# 20210903BuckModel.net
KiCad netlist of a schematic drawn in EasyEDA Pro
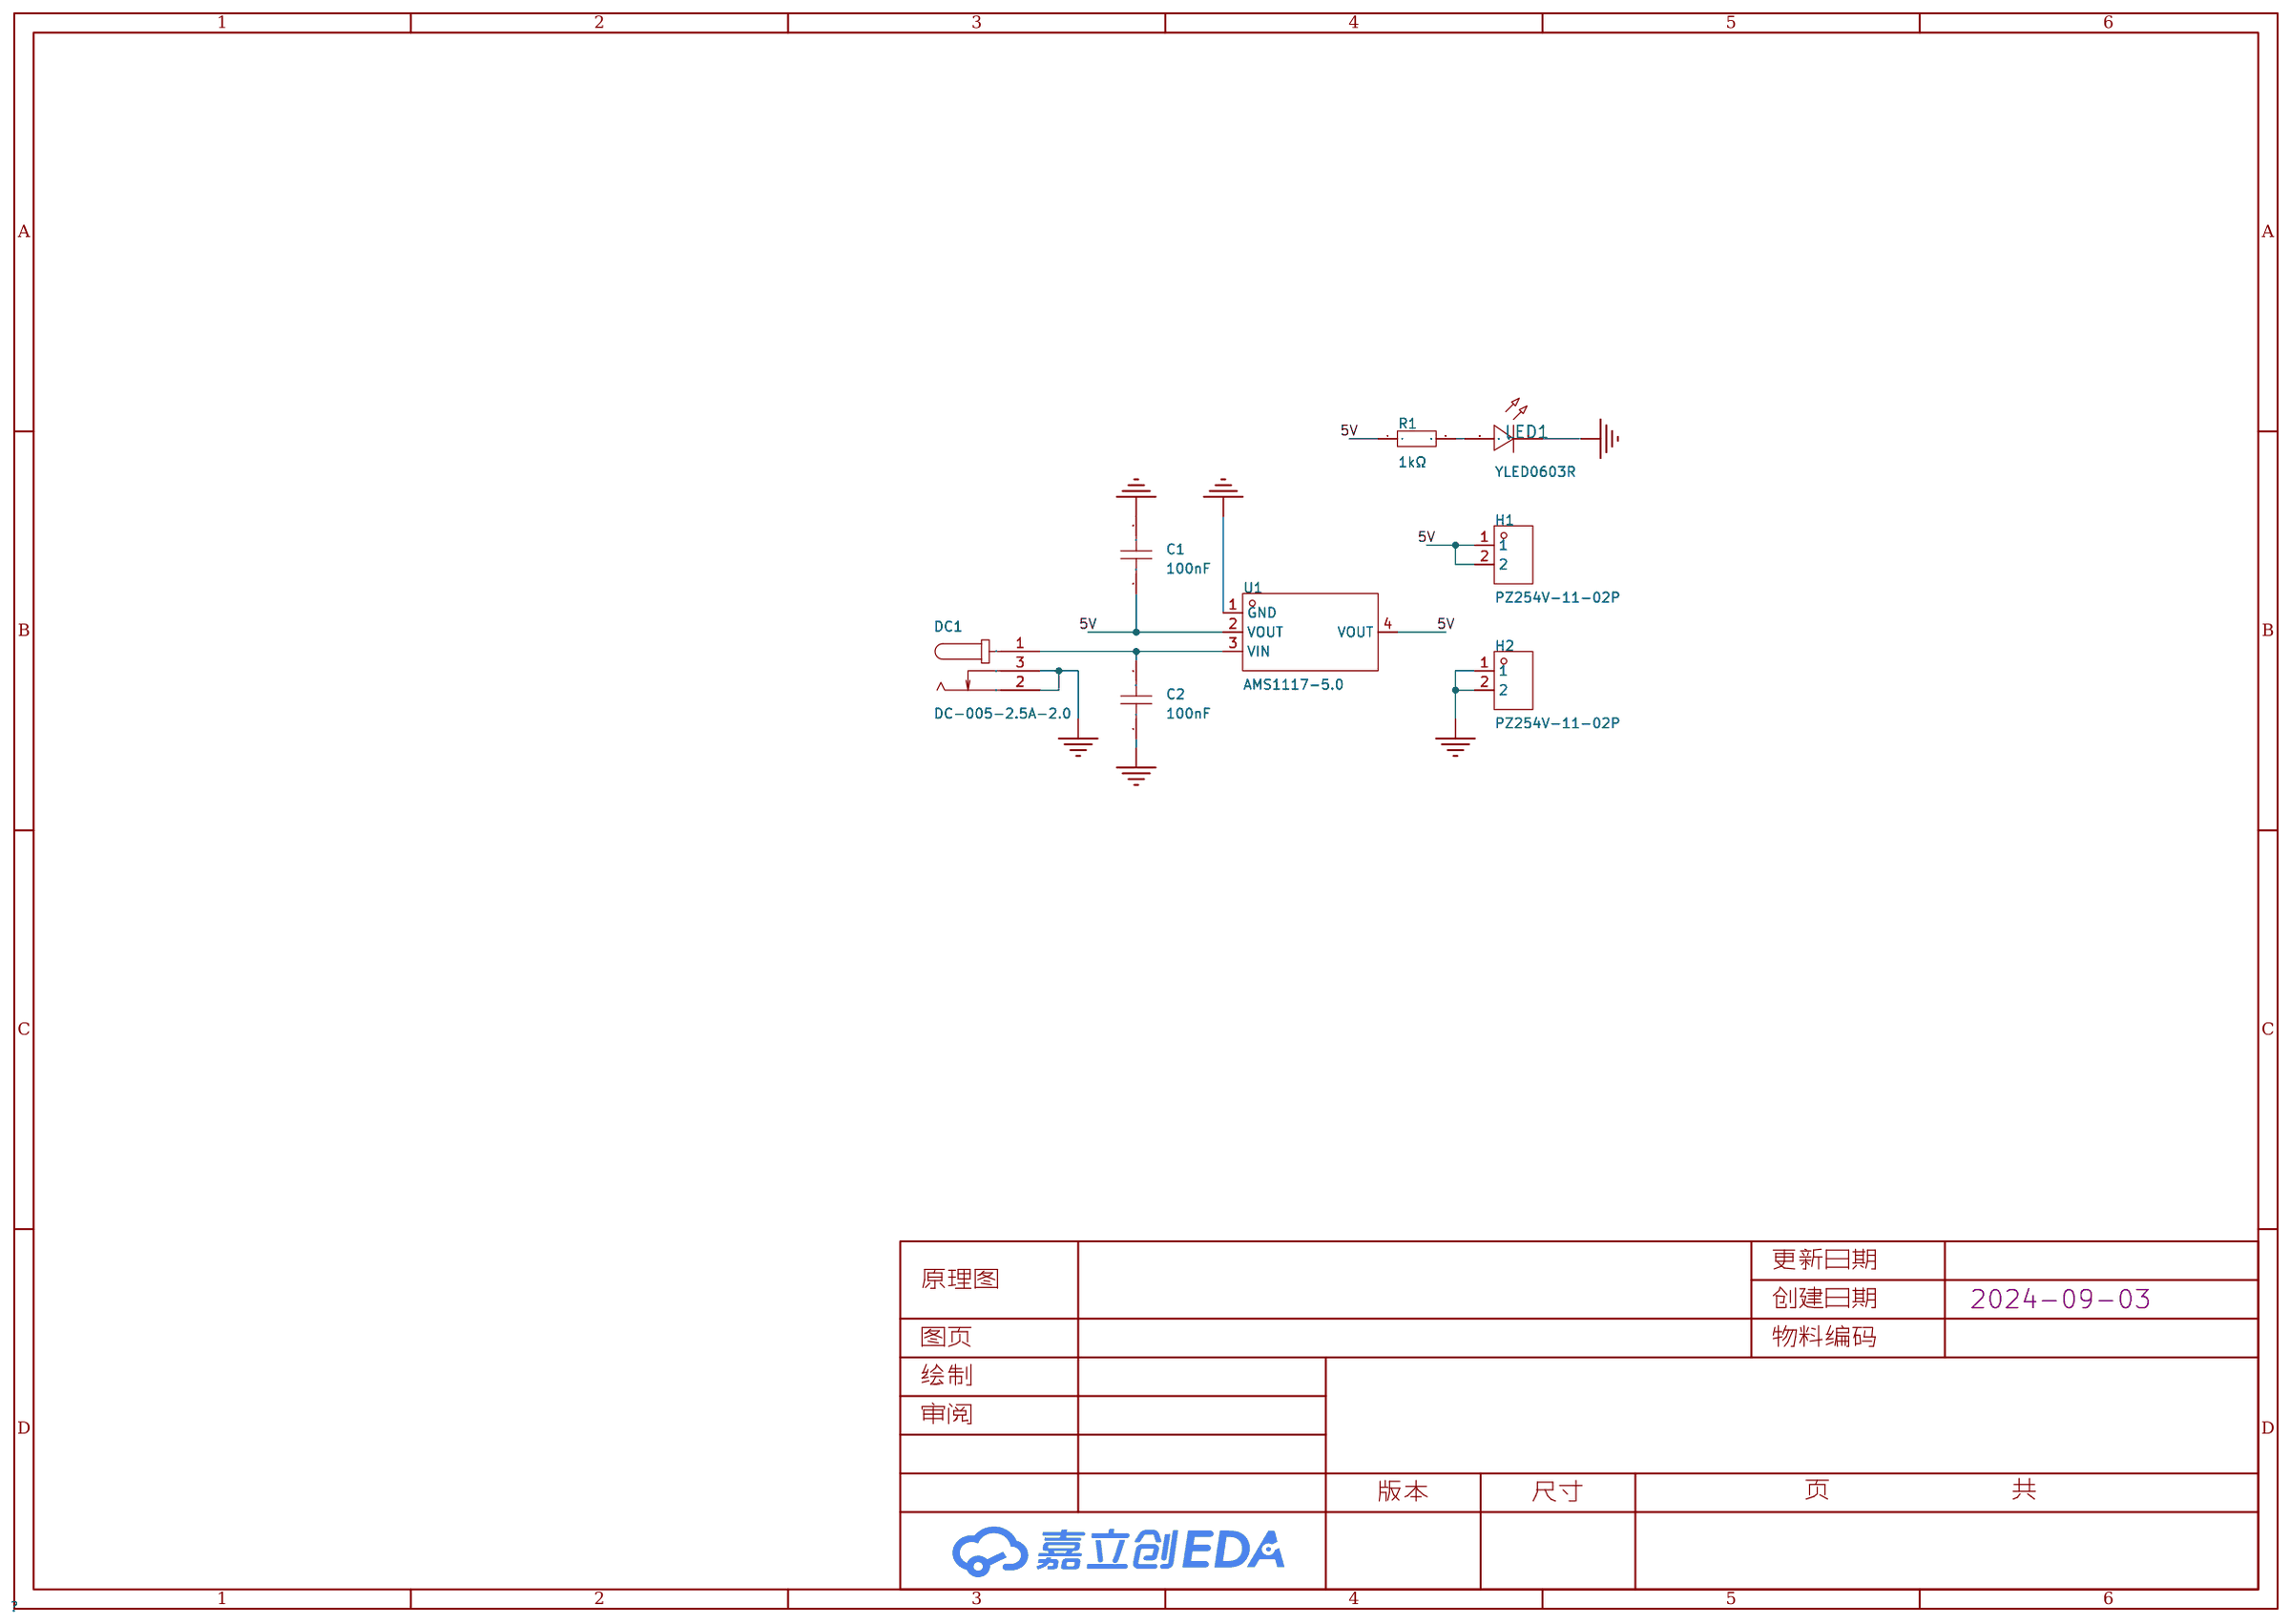
[diagram p0: schematic sheet]

(export (version "E")
  (design (tool "Eeschema 10.0.6"))
  (components
    (comp (ref "C1")
      (value "100nF")
      (footprint "easyedapro:C0402")
      (description "容值:100nF;精度:±10%;额定电压:16V;材质(温度系数):X7R;")
      (fields
        (field (name "Manufacturer Part") "CC0402KRX7R7BB104")
        (field (name "Manufacturer") "YAGEO(国巨)")
      )
      (libsource (lib "easyedapro") (part "CC0402KRX7R7BB104"))
    )
    (comp (ref "C2")
      (value "100nF")
      (footprint "easyedapro:C0402")
      (description "容值:100nF;精度:±10%;额定电压:16V;材质(温度系数):X7R;")
      (fields
        (field (name "Manufacturer Part") "CC0402KRX7R7BB104")
        (field (name "Manufacturer") "YAGEO(国巨)")
      )
      (libsource (lib "easyedapro") (part "CC0402KRX7R7BB104"))
    )
    (comp (ref "DC1")
      (value "DC-005-2.5A-2.0")
      (footprint "easyedapro:CONN-TH_DC-005-2.5A-2.0")
      (fields (field (name "Manufacturer") "XKB Connection(中国星坤)"))
      (libsource (lib "easyedapro") (part "DC-005-2.5A-2.0"))
    )
    (comp (ref "H1")
      (value "PZ254V-11-02P")
      (footprint "easyedapro:HDR-TH_2P-P2.54-V-M")
      (fields (field (name "Manufacturer") "XFCN(兴飞)"))
      (libsource (lib "easyedapro") (part "PZ254V-11-02P"))
    )
    (comp (ref "H2")
      (value "PZ254V-11-02P")
      (footprint "easyedapro:HDR-TH_2P-P2.54-V-M")
      (fields (field (name "Manufacturer") "XFCN(兴飞)"))
      (libsource (lib "easyedapro") (part "PZ254V-11-02P"))
    )
    (comp (ref "LED1")
      (value "YLED0603R")
      (footprint "easyedapro:LED_0603")
      (fields (field (name "Manufacturer") "YONGYUTAI(永裕泰)"))
      (libsource (lib "easyedapro") (part "LED_R"))
    )
    (comp (ref "R1")
      (value "1kΩ")
      (footprint "easyedapro:R0603")
      (description "电阻类型:厚膜电阻;阻值:1kΩ;精度:±1%;功率:100mW;最大工作电压:75V;温度系数:±100ppm/°C;")
      (fields
        (field (name "Manufacturer Part") "0603WAF1001T5E")
        (field (name "Manufacturer") "UNI-ROYAL(厚声)")
      )
      (libsource (lib "easyedapro") (part "0603WAF1001T5E"))
    )
    (comp (ref "U1")
      (value "AMS1117-5.0")
      (footprint "easyedapro:SOT-223_L6.5-W3.5-P2.30-LS7.0-BR")
      (description "输出类型:固定;最大输入电压:12V;输出电压:5V;最大输出电流:1A;电源纹波抑制比(PSRR):68dB@(120Hz);输出极性:正极;")
      (fields (field (name "Manufacturer") "AMS"))
      (libsource (lib "easyedapro") (part "AMS1117-5.0"))
    )
  )
  (nets
    (net (code "1") (name "/5V") (class "Default")
      (node (ref "C1") (pin "1") (pinfunction "1_1") (pintype "unspecified"))
      (node (ref "H1") (pin "1") (pinfunction "1_1") (pintype "unspecified"))
      (node (ref "H1") (pin "2") (pinfunction "2_2") (pintype "unspecified"))
      (node (ref "R1") (pin "1") (pinfunction "1_1") (pintype "input"))
      (node (ref "U1") (pin "2") (pinfunction "VOUT_2") (pintype "unspecified"))
      (node (ref "U1") (pin "4") (pinfunction "VOUT_4") (pintype "unspecified"))
    )
    (net (code "2") (name "GND") (class "Default")
      (node (ref "C1") (pin "2") (pinfunction "2_2") (pintype "unspecified"))
      (node (ref "C2") (pin "1") (pinfunction "1_1") (pintype "unspecified"))
      (node (ref "DC1") (pin "2") (pinfunction "2_2") (pintype "unspecified"))
      (node (ref "DC1") (pin "3") (pinfunction "3_3") (pintype "unspecified"))
      (node (ref "H2") (pin "1") (pinfunction "1_1") (pintype "unspecified"))
      (node (ref "H2") (pin "2") (pinfunction "2_2") (pintype "unspecified"))
      (node (ref "LED1") (pin "1") (pinfunction "C_1") (pintype "input"))
      (node (ref "U1") (pin "1") (pinfunction "GND_1") (pintype "unspecified"))
    )
    (net (code "3") (name "Net-(LED1-A)") (class "Default")
      (node (ref "LED1") (pin "2") (pinfunction "A_2") (pintype "input"))
      (node (ref "R1") (pin "2") (pinfunction "2_2") (pintype "input"))
    )
    (net (code "4") (name "Net-(U1-VIN)") (class "Default")
      (node (ref "C2") (pin "2") (pinfunction "2_2") (pintype "unspecified"))
      (node (ref "DC1") (pin "1") (pinfunction "1_1") (pintype "unspecified"))
      (node (ref "U1") (pin "3") (pinfunction "VIN_3") (pintype "unspecified"))
    )
  )
)
